# V2.net
KiCad netlist of a schematic drawn in EAGLE
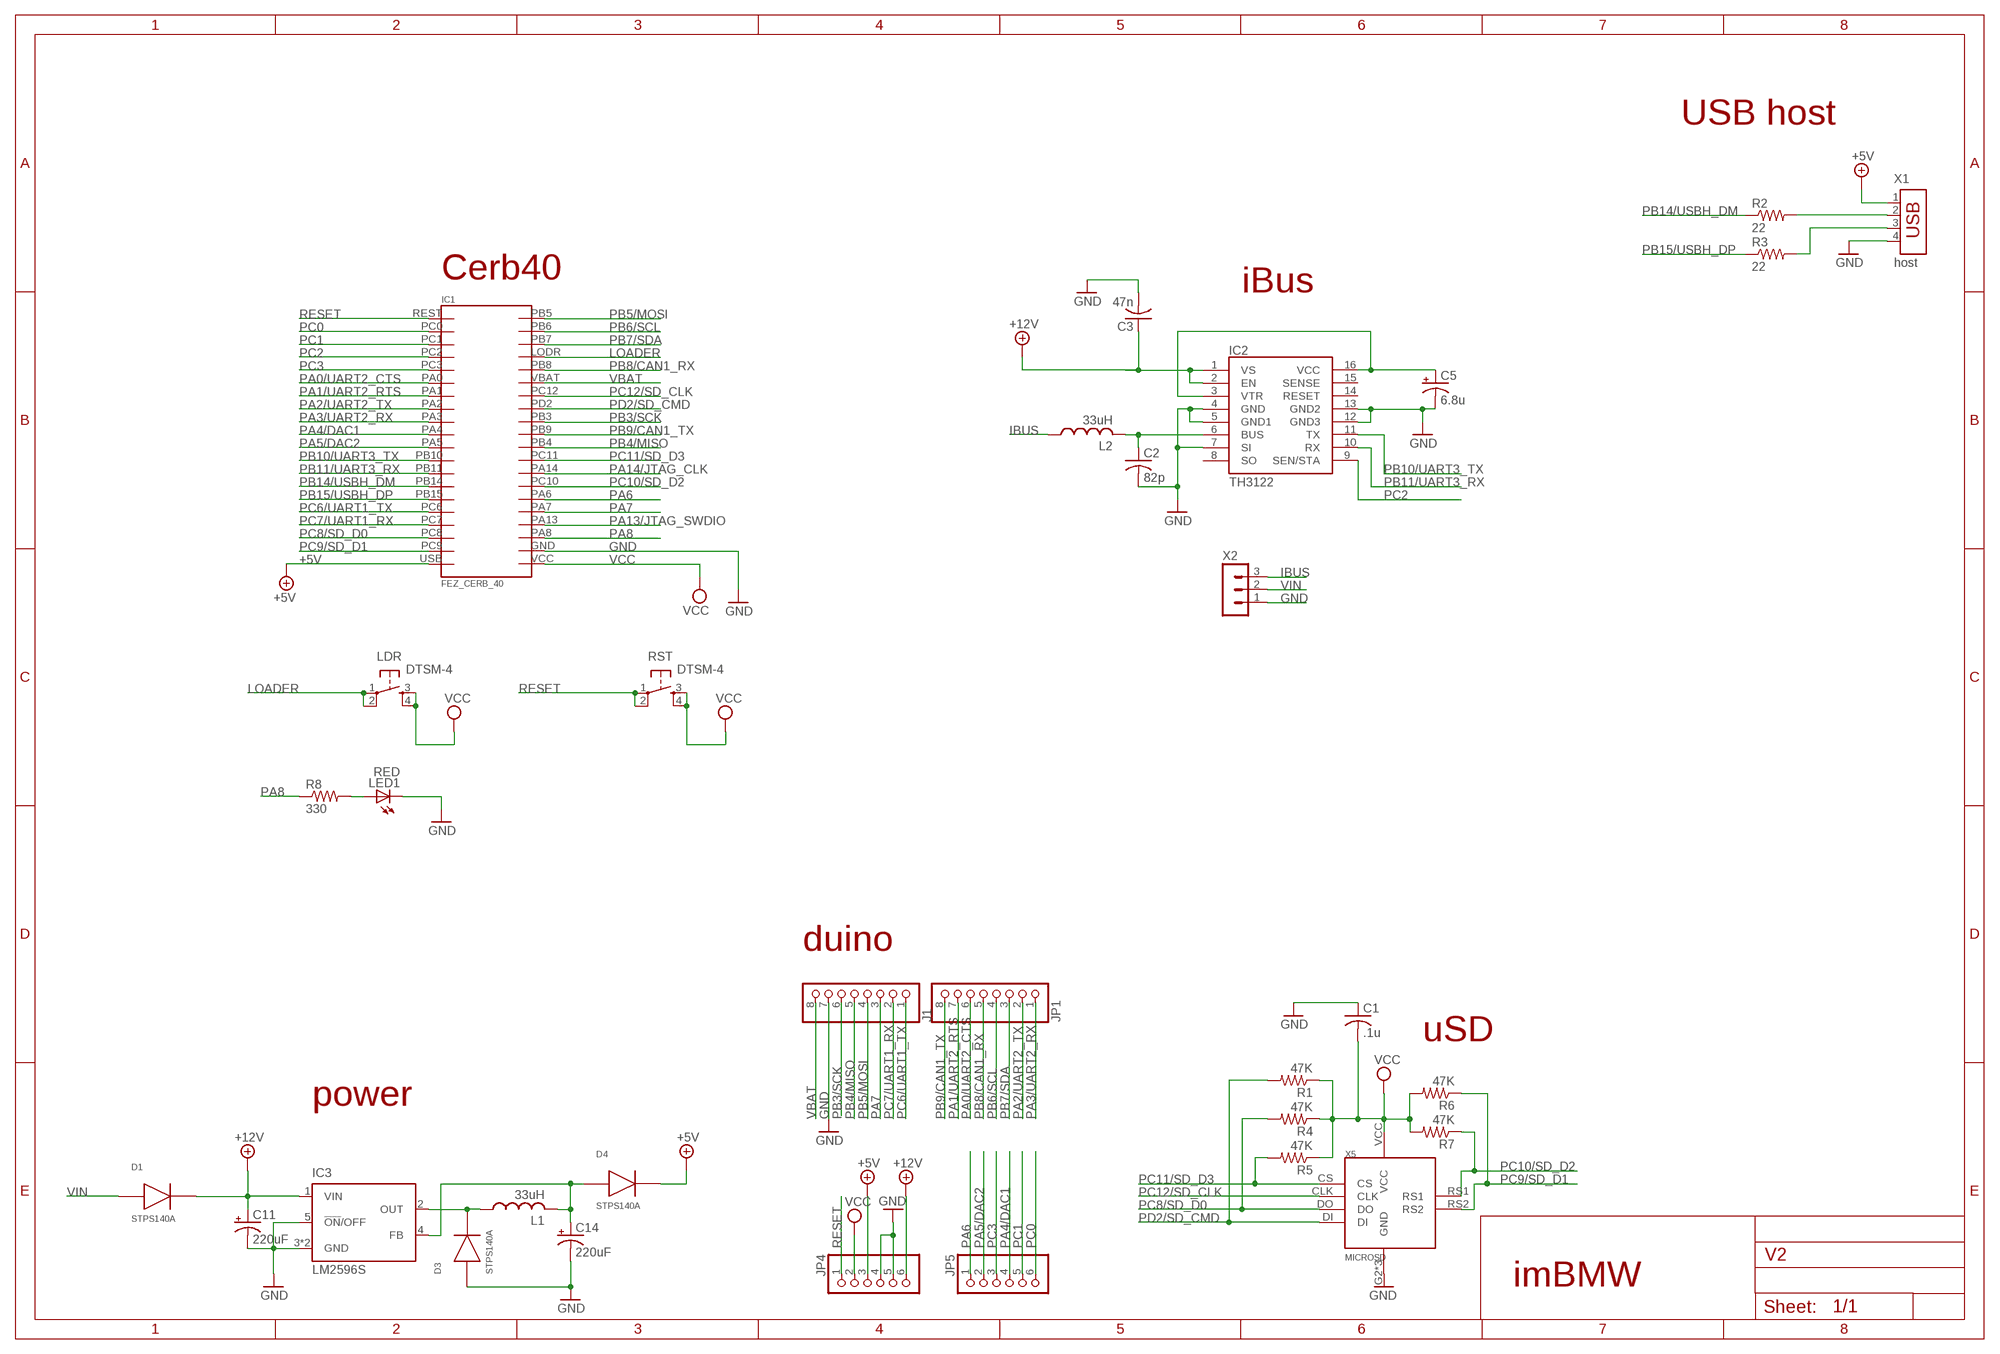
[diagram p0: schematic, sheet 1]

(export (version "E")
  (design (tool "Eeschema 10.0.6"))
  (components
    (comp (ref "C1")
      (value ".1u")
      (footprint "eagle-import:C0805")
      (libsource (lib "eagle-import") (part "C-USC0805"))
    )
    (comp (ref "C2")
      (value "82p")
      (footprint "eagle-import:C0805")
      (libsource (lib "eagle-import") (part "C-USC0805"))
    )
    (comp (ref "C3")
      (value "47n")
      (footprint "eagle-import:C0805")
      (libsource (lib "eagle-import") (part "C-USC0805"))
    )
    (comp (ref "C5")
      (value "6.8u")
      (footprint "eagle-import:SMC_B")
      (libsource (lib "eagle-import") (part "CPOL-USSMCB"))
    )
    (comp (ref "C11")
      (value "220uF")
      (footprint "eagle-import:SMC_D")
      (libsource (lib "eagle-import") (part "CPOL-USSMCD"))
    )
    (comp (ref "C14")
      (value "220uF")
      (footprint "eagle-import:SMC_D")
      (libsource (lib "eagle-import") (part "CPOL-USSMCD"))
    )
    (comp (ref "D1")
      (value "STPS140A")
      (footprint "eagle-import:DIODE_SMA")
      (libsource (lib "eagle-import") (part "DIODE_SMA"))
    )
    (comp (ref "D3")
      (value "STPS140A")
      (footprint "eagle-import:DIODE_SMA")
      (libsource (lib "eagle-import") (part "DIODE_SMA"))
    )
    (comp (ref "D4")
      (value "STPS140A")
      (footprint "eagle-import:DIODE_SMA")
      (libsource (lib "eagle-import") (part "DIODE_SMA"))
    )
    (comp (ref "IC1")
      (value "FEZ_CERB_40")
      (footprint "eagle-import:FEZ_CERB_40")
      (libsource (lib "eagle-import") (part "FEZ_CERB_40"))
    )
    (comp (ref "IC2")
      (value "TH3122")
      (footprint "eagle-import:SO16L")
      (libsource (lib "eagle-import") (part "TH3122"))
    )
    (comp (ref "IC3")
      (value "LM2596S")
      (footprint "eagle-import:TO263-5")
      (fields (field (name "MF") "NATIONAL SEMICONDUCTOR") (field (name "MPN") "LM2596S-ADJ/NOPB"))
      (libsource (lib "eagle-import") (part "LM2596S"))
    )
    (comp (ref "J1")
      (value "PINHD-1X8")
      (footprint "eagle-import:1X08")
      (libsource (lib "eagle-import") (part "PINHD-1X8"))
    )
    (comp (ref "JP1")
      (value "PINHD-1X8")
      (footprint "eagle-import:1X08")
      (libsource (lib "eagle-import") (part "PINHD-1X8"))
    )
    (comp (ref "JP4")
      (value "PINHD-1X6")
      (footprint "eagle-import:1X06")
      (libsource (lib "eagle-import") (part "PINHD-1X6"))
    )
    (comp (ref "JP5")
      (value "PINHD-1X6")
      (footprint "eagle-import:1X06")
      (libsource (lib "eagle-import") (part "PINHD-1X6"))
    )
    (comp (ref "L1")
      (value "33uH")
      (footprint "eagle-import:POWER-CHOKE_WE-TPC")
      (libsource (lib "eagle-import") (part "L-USWE-TPC"))
    )
    (comp (ref "L2")
      (value "33uH")
      (footprint "eagle-import:POWER-CHOKE_WE-TPC")
      (libsource (lib "eagle-import") (part "L-USWE-TPC"))
    )
    (comp (ref "LDR")
      (value "DTSM-4")
      (footprint "eagle-import:DTSM-4")
      (libsource (lib "eagle-import") (part "DTSM-4"))
    )
    (comp (ref "LED1")
      (value "RED")
      (footprint "eagle-import:SML0603")
      (libsource (lib "eagle-import") (part "LEDSML0603"))
    )
    (comp (ref "R1")
      (value "47K")
      (footprint "eagle-import:R0805")
      (libsource (lib "eagle-import") (part "R-US_R0805"))
    )
    (comp (ref "R2")
      (value "22")
      (footprint "eagle-import:R0805")
      (libsource (lib "eagle-import") (part "R-US_R0805"))
    )
    (comp (ref "R3")
      (value "22")
      (footprint "eagle-import:R0805")
      (libsource (lib "eagle-import") (part "R-US_R0805"))
    )
    (comp (ref "R4")
      (value "47K")
      (footprint "eagle-import:R0805")
      (libsource (lib "eagle-import") (part "R-US_R0805"))
    )
    (comp (ref "R5")
      (value "47K")
      (footprint "eagle-import:R0805")
      (libsource (lib "eagle-import") (part "R-US_R0805"))
    )
    (comp (ref "R6")
      (value "47K")
      (footprint "eagle-import:R0805")
      (libsource (lib "eagle-import") (part "R-US_R0805"))
    )
    (comp (ref "R7")
      (value "47K")
      (footprint "eagle-import:R0805")
      (libsource (lib "eagle-import") (part "R-US_R0805"))
    )
    (comp (ref "R8")
      (value "330")
      (footprint "eagle-import:R0805")
      (libsource (lib "eagle-import") (part "R-US_R0805"))
    )
    (comp (ref "RST")
      (value "DTSM-4")
      (footprint "eagle-import:DTSM-4")
      (libsource (lib "eagle-import") (part "DTSM-4"))
    )
    (comp (ref "X1")
      (value "host")
      (footprint "eagle-import:USB")
      (libsource (lib "eagle-import") (part "USB-787616"))
    )
    (comp (ref "X2")
      (value "MA03-1")
      (footprint "eagle-import:MA03-1")
      (libsource (lib "eagle-import") (part "MA03-1"))
    )
    (comp (ref "X5")
      (value "MICROSD")
      (footprint "eagle-import:MICROSD")
      (libsource (lib "eagle-import") (part "MICROSD"))
    )
  )
  (nets
    (net (code "1") (name "+5V") (class "Default")
      (node (ref "D4") (pin "K") (pinfunction "K_K") (pintype "bidirectional"))
      (node (ref "IC1") (pin "USB") (pinfunction "USB_USB") (pintype "bidirectional"))
      (node (ref "JP4") (pin "3") (pinfunction "3_3") (pintype "passive"))
      (node (ref "X1") (pin "1") (pinfunction "1_1") (pintype "passive"))
    )
    (net (code "2") (name "+12V") (class "Default")
      (node (ref "C11") (pin "+") (pinfunction "+_+") (pintype "passive"))
      (node (ref "C3") (pin "1") (pinfunction "1_1") (pintype "passive"))
      (node (ref "D1") (pin "K") (pinfunction "K_K") (pintype "bidirectional"))
      (node (ref "IC2") (pin "1") (pinfunction "VS_1") (pintype "power_in"))
      (node (ref "IC2") (pin "2") (pinfunction "EN_2") (pintype "input"))
      (node (ref "IC3") (pin "1") (pinfunction "VIN_1") (pintype "input"))
      (node (ref "JP4") (pin "6") (pinfunction "6_6") (pintype "passive"))
    )
    (net (code "3") (name "/IBUS") (class "Default")
      (node (ref "L2") (pin "1") (pinfunction "1_1") (pintype "passive"))
      (node (ref "X2") (pin "3") (pinfunction "3_3") (pintype "passive"))
    )
    (net (code "4") (name "/LOADER") (class "Default")
      (node (ref "IC1") (pin "LODR") (pinfunction "LODR_LODR") (pintype "bidirectional"))
      (node (ref "LDR") (pin "1") (pinfunction "1_1") (pintype "passive"))
      (node (ref "LDR") (pin "2") (pinfunction "2_2") (pintype "passive"))
    )
    (net (code "5") (name "/PA0{slash}UART2_CTS") (class "Default")
      (node (ref "IC1") (pin "PA0") (pinfunction "PA0_PA0") (pintype "bidirectional"))
      (node (ref "JP1") (pin "6") (pinfunction "6_6") (pintype "passive"))
    )
    (net (code "6") (name "/PA1{slash}UART2_RTS") (class "Default")
      (node (ref "IC1") (pin "PA1") (pinfunction "PA1_PA1") (pintype "bidirectional"))
      (node (ref "JP1") (pin "7") (pinfunction "7_7") (pintype "passive"))
    )
    (net (code "7") (name "/PA2{slash}UART2_TX") (class "Default")
      (node (ref "IC1") (pin "PA2") (pinfunction "PA2_PA2") (pintype "bidirectional"))
      (node (ref "JP1") (pin "2") (pinfunction "2_2") (pintype "passive"))
    )
    (net (code "8") (name "/PA3{slash}UART2_RX") (class "Default")
      (node (ref "IC1") (pin "PA3") (pinfunction "PA3_PA3") (pintype "bidirectional"))
      (node (ref "JP1") (pin "1") (pinfunction "1_1") (pintype "passive"))
    )
    (net (code "9") (name "/PA4{slash}DAC1") (class "Default")
      (node (ref "IC1") (pin "PA4") (pinfunction "PA4_PA4") (pintype "bidirectional"))
      (node (ref "JP5") (pin "4") (pinfunction "4_4") (pintype "passive"))
    )
    (net (code "10") (name "/PA5{slash}DAC2") (class "Default")
      (node (ref "IC1") (pin "PA5") (pinfunction "PA5_PA5") (pintype "bidirectional"))
      (node (ref "JP5") (pin "2") (pinfunction "2_2") (pintype "passive"))
    )
    (net (code "11") (name "/PA6") (class "Default")
      (node (ref "IC1") (pin "PA6") (pinfunction "PA6_PA6") (pintype "bidirectional"))
      (node (ref "JP5") (pin "1") (pinfunction "1_1") (pintype "passive"))
    )
    (net (code "12") (name "/PA7") (class "Default")
      (node (ref "IC1") (pin "PA7") (pinfunction "PA7_PA7") (pintype "bidirectional"))
      (node (ref "J1") (pin "3") (pinfunction "3_3") (pintype "passive"))
    )
    (net (code "13") (name "/PA8") (class "Default")
      (node (ref "IC1") (pin "PA8") (pinfunction "PA8_PA8") (pintype "bidirectional"))
      (node (ref "R8") (pin "1") (pinfunction "1_1") (pintype "passive"))
    )
    (net (code "14") (name "/PA13{slash}JTAG_SWDIO") (class "Default")
      (node (ref "IC1") (pin "PA13") (pinfunction "PA13_PA13") (pintype "bidirectional"))
    )
    (net (code "15") (name "/PA14{slash}JTAG_CLK") (class "Default")
      (node (ref "IC1") (pin "PA14") (pinfunction "PA14_PA14") (pintype "bidirectional"))
    )
    (net (code "16") (name "/PB3{slash}SCK") (class "Default")
      (node (ref "IC1") (pin "PB3") (pinfunction "PB3_PB3") (pintype "bidirectional"))
      (node (ref "J1") (pin "6") (pinfunction "6_6") (pintype "passive"))
    )
    (net (code "17") (name "/PB4{slash}MISO") (class "Default")
      (node (ref "IC1") (pin "PB4") (pinfunction "PB4_PB4") (pintype "bidirectional"))
      (node (ref "J1") (pin "5") (pinfunction "5_5") (pintype "passive"))
    )
    (net (code "18") (name "/PB5{slash}MOSI") (class "Default")
      (node (ref "IC1") (pin "PB5") (pinfunction "PB5_PB5") (pintype "bidirectional"))
      (node (ref "J1") (pin "4") (pinfunction "4_4") (pintype "passive"))
    )
    (net (code "19") (name "/PB6{slash}SCL") (class "Default")
      (node (ref "IC1") (pin "PB6") (pinfunction "PB6_PB6") (pintype "bidirectional"))
      (node (ref "JP1") (pin "4") (pinfunction "4_4") (pintype "passive"))
    )
    (net (code "20") (name "/PB7{slash}SDA") (class "Default")
      (node (ref "IC1") (pin "PB7") (pinfunction "PB7_PB7") (pintype "bidirectional"))
      (node (ref "JP1") (pin "3") (pinfunction "3_3") (pintype "passive"))
    )
    (net (code "21") (name "/PB8{slash}CAN1_RX") (class "Default")
      (node (ref "IC1") (pin "PB8") (pinfunction "PB8_PB8") (pintype "bidirectional"))
      (node (ref "JP1") (pin "5") (pinfunction "5_5") (pintype "passive"))
    )
    (net (code "22") (name "/PB9{slash}CAN1_TX") (class "Default")
      (node (ref "IC1") (pin "PB9") (pinfunction "PB9_PB9") (pintype "bidirectional"))
      (node (ref "JP1") (pin "8") (pinfunction "8_8") (pintype "passive"))
    )
    (net (code "23") (name "/PB10{slash}UART3_TX") (class "Default")
      (node (ref "IC1") (pin "PB10") (pinfunction "PB10_PB10") (pintype "bidirectional"))
      (node (ref "IC2") (pin "11") (pinfunction "TX_11") (pintype "input"))
    )
    (net (code "24") (name "/PB11{slash}UART3_RX") (class "Default")
      (node (ref "IC1") (pin "PB11") (pinfunction "PB11_PB11") (pintype "bidirectional"))
      (node (ref "IC2") (pin "10") (pinfunction "RX_10") (pintype "output"))
    )
    (net (code "25") (name "/PB14{slash}USBH_DM") (class "Default")
      (node (ref "IC1") (pin "PB14") (pinfunction "PB14_PB14") (pintype "bidirectional"))
      (node (ref "R2") (pin "1") (pinfunction "1_1") (pintype "passive"))
    )
    (net (code "26") (name "/PB15{slash}USBH_DP") (class "Default")
      (node (ref "IC1") (pin "PB15") (pinfunction "PB15_PB15") (pintype "bidirectional"))
      (node (ref "R3") (pin "1") (pinfunction "1_1") (pintype "passive"))
    )
    (net (code "27") (name "/PC0") (class "Default")
      (node (ref "IC1") (pin "PC0") (pinfunction "PC0_PC0") (pintype "bidirectional"))
      (node (ref "JP5") (pin "6") (pinfunction "6_6") (pintype "passive"))
    )
    (net (code "28") (name "/PC1") (class "Default")
      (node (ref "IC1") (pin "PC1") (pinfunction "PC1_PC1") (pintype "bidirectional"))
      (node (ref "JP5") (pin "5") (pinfunction "5_5") (pintype "passive"))
    )
    (net (code "29") (name "/PC2") (class "Default")
      (node (ref "IC1") (pin "PC2") (pinfunction "PC2_PC2") (pintype "bidirectional"))
      (node (ref "IC2") (pin "9") (pinfunction "SEN/STA_9") (pintype "bidirectional"))
    )
    (net (code "30") (name "/PC3") (class "Default")
      (node (ref "IC1") (pin "PC3") (pinfunction "PC3_PC3") (pintype "bidirectional"))
      (node (ref "JP5") (pin "3") (pinfunction "3_3") (pintype "passive"))
    )
    (net (code "31") (name "/PC6{slash}UART1_TX") (class "Default")
      (node (ref "IC1") (pin "PC6") (pinfunction "PC6_PC6") (pintype "bidirectional"))
      (node (ref "J1") (pin "1") (pinfunction "1_1") (pintype "passive"))
    )
    (net (code "32") (name "/PC7{slash}UART1_RX") (class "Default")
      (node (ref "IC1") (pin "PC7") (pinfunction "PC7_PC7") (pintype "bidirectional"))
      (node (ref "J1") (pin "2") (pinfunction "2_2") (pintype "passive"))
    )
    (net (code "33") (name "/PC8{slash}SD_D0") (class "Default")
      (node (ref "IC1") (pin "PC8") (pinfunction "PC8_PC8") (pintype "bidirectional"))
      (node (ref "R4") (pin "2") (pinfunction "2_2") (pintype "passive"))
      (node (ref "X5") (pin "DO") (pinfunction "DO_DO") (pintype "bidirectional"))
    )
    (net (code "34") (name "/PC9{slash}SD_D1") (class "Default")
      (node (ref "IC1") (pin "PC9") (pinfunction "PC9_PC9") (pintype "bidirectional"))
      (node (ref "R6") (pin "1") (pinfunction "1_1") (pintype "passive"))
      (node (ref "X5") (pin "RS2") (pinfunction "RS2_RS2") (pintype "bidirectional"))
    )
    (net (code "35") (name "/PC10{slash}SD_D2") (class "Default")
      (node (ref "IC1") (pin "PC10") (pinfunction "PC10_PC10") (pintype "bidirectional"))
      (node (ref "R7") (pin "1") (pinfunction "1_1") (pintype "passive"))
      (node (ref "X5") (pin "RS1") (pinfunction "RS1_RS1") (pintype "bidirectional"))
    )
    (net (code "36") (name "/PC11{slash}SD_D3") (class "Default")
      (node (ref "IC1") (pin "PC11") (pinfunction "PC11_PC11") (pintype "bidirectional"))
      (node (ref "R5") (pin "2") (pinfunction "2_2") (pintype "passive"))
      (node (ref "X5") (pin "CS") (pinfunction "CS_CS") (pintype "bidirectional"))
    )
    (net (code "37") (name "/PC12{slash}SD_CLK") (class "Default")
      (node (ref "IC1") (pin "PC12") (pinfunction "PC12_PC12") (pintype "bidirectional"))
      (node (ref "X5") (pin "CLK") (pinfunction "CLK_CLK") (pintype "bidirectional"))
    )
    (net (code "38") (name "/PD2{slash}SD_CMD") (class "Default")
      (node (ref "IC1") (pin "PD2") (pinfunction "PD2_PD2") (pintype "bidirectional"))
      (node (ref "R1") (pin "2") (pinfunction "2_2") (pintype "passive"))
      (node (ref "X5") (pin "DI") (pinfunction "DI_DI") (pintype "bidirectional"))
    )
    (net (code "39") (name "/RESET") (class "Default")
      (node (ref "IC1") (pin "REST") (pinfunction "REST_REST") (pintype "bidirectional"))
      (node (ref "JP4") (pin "1") (pinfunction "1_1") (pintype "passive"))
      (node (ref "RST") (pin "1") (pinfunction "1_1") (pintype "passive"))
      (node (ref "RST") (pin "2") (pinfunction "2_2") (pintype "passive"))
    )
    (net (code "40") (name "/VBAT") (class "Default")
      (node (ref "IC1") (pin "VBAT") (pinfunction "VBAT_VBAT") (pintype "bidirectional"))
      (node (ref "J1") (pin "8") (pinfunction "8_8") (pintype "passive"))
    )
    (net (code "41") (name "/VIN") (class "Default")
      (node (ref "D1") (pin "A") (pinfunction "A_A") (pintype "bidirectional"))
      (node (ref "X2") (pin "2") (pinfunction "2_2") (pintype "passive"))
    )
    (net (code "42") (name "GND") (class "Default")
      (node (ref "C1") (pin "1") (pinfunction "1_1") (pintype "passive"))
      (node (ref "C11") (pin "-") (pinfunction "-_-") (pintype "passive"))
      (node (ref "C14") (pin "-") (pinfunction "-_-") (pintype "passive"))
      (node (ref "C2") (pin "2") (pinfunction "2_2") (pintype "passive"))
      (node (ref "C3") (pin "2") (pinfunction "2_2") (pintype "passive"))
      (node (ref "C5") (pin "-") (pinfunction "-_-") (pintype "passive"))
      (node (ref "D3") (pin "A") (pinfunction "A_A") (pintype "bidirectional"))
      (node (ref "IC1") (pin "GND") (pinfunction "GND_GND") (pintype "bidirectional"))
      (node (ref "IC2") (pin "12") (pinfunction "GND3_12") (pintype "bidirectional"))
      (node (ref "IC2") (pin "13") (pinfunction "GND2_13") (pintype "bidirectional"))
      (node (ref "IC2") (pin "4") (pinfunction "GND_4") (pintype "bidirectional"))
      (node (ref "IC2") (pin "5") (pinfunction "GND1_5") (pintype "bidirectional"))
      (node (ref "IC2") (pin "7") (pinfunction "SI_7") (pintype "input"))
      (node (ref "IC3") (pin "3") (pinfunction "GND_3") (pintype "power_in"))
      (node (ref "IC3") (pin "5") (pinfunction "~{ON}/OFF_5") (pintype "input"))
      (node (ref "IC3") (pin "6") (pinfunction "GND_6") (pintype "power_in"))
      (node (ref "J1") (pin "7") (pinfunction "7_7") (pintype "passive"))
      (node (ref "JP4") (pin "4") (pinfunction "4_4") (pintype "passive"))
      (node (ref "JP4") (pin "5") (pinfunction "5_5") (pintype "passive"))
      (node (ref "LED1") (pin "C") (pinfunction "C_C") (pintype "passive"))
      (node (ref "X1") (pin "4") (pinfunction "4_4") (pintype "passive"))
      (node (ref "X2") (pin "1") (pinfunction "1_1") (pintype "passive"))
      (node (ref "X5") (pin "G2") (pinfunction "GND_G2") (pintype "bidirectional"))
      (node (ref "X5") (pin "G3") (pinfunction "GND_G3") (pintype "bidirectional"))
      (node (ref "X5") (pin "GND") (pinfunction "GND_GND") (pintype "bidirectional"))
    )
    (net (code "43") (name "Net-(IC2-BUS)") (class "Default")
      (node (ref "C2") (pin "1") (pinfunction "1_1") (pintype "passive"))
      (node (ref "IC2") (pin "6") (pinfunction "BUS_6") (pintype "bidirectional"))
      (node (ref "L2") (pin "2") (pinfunction "2_2") (pintype "passive"))
    )
    (net (code "44") (name "Net-(IC2-VCC)") (class "Default")
      (node (ref "C5") (pin "+") (pinfunction "+_+") (pintype "passive"))
      (node (ref "IC2") (pin "16") (pinfunction "VCC_16") (pintype "output"))
      (node (ref "IC2") (pin "3") (pinfunction "VTR_3") (pintype "input"))
    )
    (net (code "45") (name "Net-(IC3-FB)") (class "Default")
      (node (ref "C14") (pin "+") (pinfunction "+_+") (pintype "passive"))
      (node (ref "D4") (pin "A") (pinfunction "A_A") (pintype "bidirectional"))
      (node (ref "IC3") (pin "4") (pinfunction "FB_4") (pintype "input"))
      (node (ref "L1") (pin "2") (pinfunction "2_2") (pintype "passive"))
    )
    (net (code "46") (name "Net-(IC3-OUT)") (class "Default")
      (node (ref "D3") (pin "K") (pinfunction "K_K") (pintype "bidirectional"))
      (node (ref "IC3") (pin "2") (pinfunction "OUT_2") (pintype "output"))
      (node (ref "L1") (pin "1") (pinfunction "1_1") (pintype "passive"))
    )
    (net (code "47") (name "Net-(LED1-PadA)") (class "Default")
      (node (ref "LED1") (pin "A") (pinfunction "A_A") (pintype "passive"))
      (node (ref "R8") (pin "2") (pinfunction "2_2") (pintype "passive"))
    )
    (net (code "48") (name "Net-(R2-Pad2)") (class "Default")
      (node (ref "R2") (pin "2") (pinfunction "2_2") (pintype "passive"))
      (node (ref "X1") (pin "2") (pinfunction "2_2") (pintype "passive"))
    )
    (net (code "49") (name "Net-(R3-Pad2)") (class "Default")
      (node (ref "R3") (pin "2") (pinfunction "2_2") (pintype "passive"))
      (node (ref "X1") (pin "3") (pinfunction "3_3") (pintype "passive"))
    )
    (net (code "50") (name "VCC") (class "Default")
      (node (ref "C1") (pin "2") (pinfunction "2_2") (pintype "passive"))
      (node (ref "IC1") (pin "VCC") (pinfunction "VCC_VCC") (pintype "bidirectional"))
      (node (ref "JP4") (pin "2") (pinfunction "2_2") (pintype "passive"))
      (node (ref "LDR") (pin "3") (pinfunction "3_3") (pintype "passive"))
      (node (ref "LDR") (pin "4") (pinfunction "4_4") (pintype "passive"))
      (node (ref "R1") (pin "1") (pinfunction "1_1") (pintype "passive"))
      (node (ref "R4") (pin "1") (pinfunction "1_1") (pintype "passive"))
      (node (ref "R5") (pin "1") (pinfunction "1_1") (pintype "passive"))
      (node (ref "R6") (pin "2") (pinfunction "2_2") (pintype "passive"))
      (node (ref "R7") (pin "2") (pinfunction "2_2") (pintype "passive"))
      (node (ref "RST") (pin "3") (pinfunction "3_3") (pintype "passive"))
      (node (ref "RST") (pin "4") (pinfunction "4_4") (pintype "passive"))
      (node (ref "X5") (pin "VCC") (pinfunction "VCC_VCC") (pintype "bidirectional"))
    )
    (net (code "51") (name "unconnected-(IC2-RESET-Pad14)") (class "Default")
      (node (ref "IC2") (pin "14") (pinfunction "RESET_14") (pintype "output"))
    )
    (net (code "52") (name "unconnected-(IC2-SENSE-Pad15)") (class "Default")
      (node (ref "IC2") (pin "15") (pinfunction "SENSE_15") (pintype "output"))
    )
    (net (code "53") (name "unconnected-(IC2-SO-Pad8)") (class "Default")
      (node (ref "IC2") (pin "8") (pinfunction "SO_8") (pintype "output"))
    )
  )
)
